# Master_MCU_ICSP_Communication.net
KiCad netlist of a schematic drawn in Altium Designer
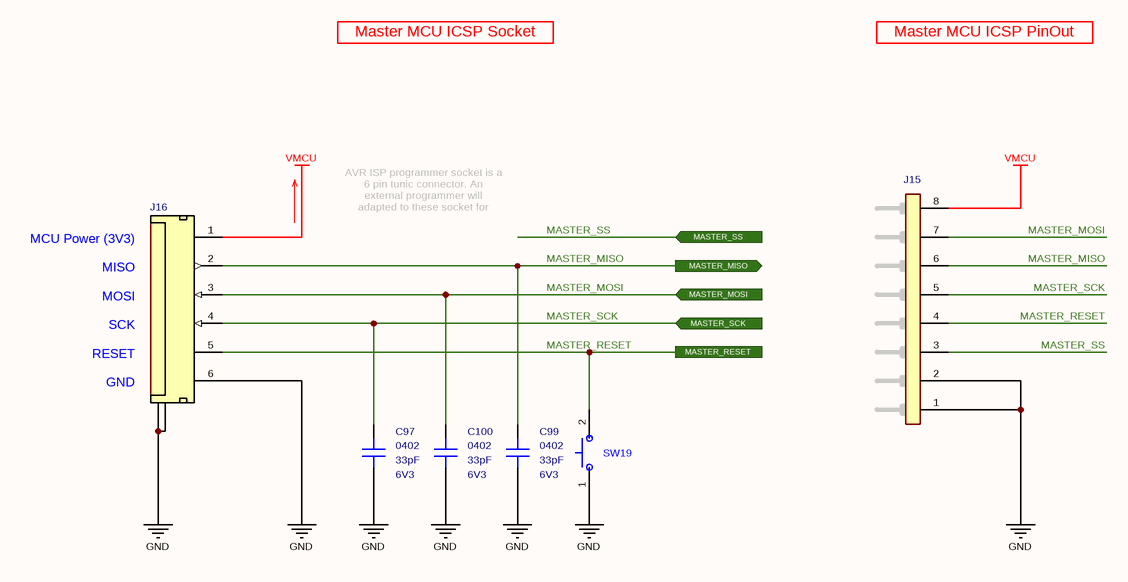
[diagram p0: Master MCU ICSP Communication.SchDoc]

(export (version "E")
  (design (tool "Eeschema 10.0.6"))
  (components
    (comp (ref "C97")
      (value "33pF")
      (footprint "CAPACITOR_0402")
      (description "Capacitor - 33pF [0402] (Ceramic)")
      (fields
        (field (name "MANUFACTURER_PART_NUMBER") "C0402C330J9RACAUTO")
        (field (name "MOUSER_PART_NUMBER") "80-C0402C330J9RAUTO")
        (field (name "CASE") "0402")
        (field (name "VOLTAGE") "6V3")
      )
      (libsource (lib "Ovoo_Schematic") (part "Capacitor - 33pF [0402-6V3]"))
    )
    (comp (ref "C99")
      (value "33pF")
      (footprint "CAPACITOR_0402")
      (description "Capacitor - 33pF [0402] (Ceramic)")
      (fields
        (field (name "MANUFACTURER_PART_NUMBER") "C0402C330J9RACAUTO")
        (field (name "MOUSER_PART_NUMBER") "80-C0402C330J9RAUTO")
        (field (name "CASE") "0402")
        (field (name "VOLTAGE") "6V3")
      )
      (libsource (lib "Ovoo_Schematic") (part "Capacitor - 33pF [0402-6V3]"))
    )
    (comp (ref "C100")
      (value "33pF")
      (footprint "CAPACITOR_0402")
      (description "Capacitor - 33pF [0402] (Ceramic)")
      (fields
        (field (name "MANUFACTURER_PART_NUMBER") "C0402C330J9RACAUTO")
        (field (name "MOUSER_PART_NUMBER") "80-C0402C330J9RAUTO")
        (field (name "CASE") "0402")
        (field (name "VOLTAGE") "6V3")
      )
      (libsource (lib "Ovoo_Schematic") (part "Capacitor - 33pF [0402-6V3]"))
    )
    (comp (ref "J15")
      (value "2.54 mm Pitch 8P Male Connector")
      (footprint "8P Header")
      (description "Headers & Wire Housings BREAKAWAY HDR VERT 8")
      (fields
        (field (name "MANUFACTURER PART NUMBER") "22-28-4083")
        (field (name "MOUSER PART NUMBER") "538-22-28-4083")
      )
      (libsource (lib "Ovoo_Library") (part "Connector - Male Header 8P (2.54)"))
    )
    (comp (ref "J16")
      (value "6P Tunic Connector")
      (footprint "Connector_Tunic 6P - H")
      (description "Mini Tunic Connector with 6P")
      (fields (field (name "MANUFACTURER_PART_NUMBER") "53261-0671"))
      (libsource (lib "Ovoo_Schematic") (part "Connector - Mini Tunic 6P (1.25)"))
    )
    (comp (ref "SW19")
      (value "Tactile Switches")
      (footprint "PTS526_Switch")
      (description "Tactile Switches 50mA 12VDC, 5.2x5.2mm, 0.8mm H, 260gf, G leads.")
      (fields
        (field (name "MANUFACTURER PART NUMBER") "PTS526 SK08 SMTR2 LFS")
        (field (name "MOUSER PART NUMBER") "611-PTS526SK08SMTR2L")
      )
      (libsource (lib "Ovoo_Library") (part "Switch - Tactile"))
    )
  )
  (nets
    (net (code "1") (name "/MASTER_MISO") (class "Default")
      (node (ref "C99") (pin "1") (pinfunction "1_1") (pintype "passive"))
      (node (ref "J15") (pin "6") (pinfunction "Pin-6_6") (pintype "passive"))
      (node (ref "J16") (pin "2") (pinfunction "M_DRV_2") (pintype "output"))
    )
    (net (code "2") (name "/MASTER_MOSI") (class "Default")
      (node (ref "C100") (pin "1") (pinfunction "1_1") (pintype "passive"))
      (node (ref "J15") (pin "7") (pinfunction "Pin-7_7") (pintype "passive"))
      (node (ref "J16") (pin "3") (pinfunction "M_DRV_3") (pintype "input"))
    )
    (net (code "3") (name "/MASTER_RESET") (class "Default")
      (node (ref "J15") (pin "4") (pinfunction "Pin-4_4") (pintype "passive"))
      (node (ref "J16") (pin "5") (pinfunction "M_DRV_5") (pintype "passive"))
      (node (ref "SW19") (pin "2") (pinfunction "COM_2") (pintype "passive"))
    )
    (net (code "4") (name "/MASTER_SCK") (class "Default")
      (node (ref "C97") (pin "1") (pinfunction "1_1") (pintype "passive"))
      (node (ref "J15") (pin "5") (pinfunction "Pin-5_5") (pintype "passive"))
      (node (ref "J16") (pin "4") (pinfunction "M_DRV_4") (pintype "input"))
    )
    (net (code "5") (name "/MASTER_SS") (class "Default")
      (node (ref "J15") (pin "3") (pinfunction "Pin-3_3") (pintype "passive"))
    )
    (net (code "6") (name "GND") (class "Default")
      (node (ref "C100") (pin "2") (pinfunction "2_2") (pintype "passive"))
      (node (ref "C97") (pin "2") (pinfunction "2_2") (pintype "passive"))
      (node (ref "C99") (pin "2") (pinfunction "2_2") (pintype "passive"))
      (node (ref "J15") (pin "1") (pinfunction "Pin-1_1") (pintype "passive"))
      (node (ref "J15") (pin "2") (pinfunction "Pin-2_2") (pintype "passive"))
      (node (ref "J16") (pin "6") (pinfunction "M_DRV_6") (pintype "passive"))
      (node (ref "J16") (pin "7") (pinfunction "GND_7") (pintype "passive"))
      (node (ref "J16") (pin "8") (pinfunction "GND_8") (pintype "passive"))
      (node (ref "SW19") (pin "1") (pinfunction "NC_1") (pintype "passive"))
    )
    (net (code "7") (name "VMCU") (class "Default")
      (node (ref "J15") (pin "8") (pinfunction "Pin-8_8") (pintype "passive"))
      (node (ref "J16") (pin "1") (pinfunction "VBAT_1") (pintype "passive"))
    )
  )
)
